# pcb.net
KiCad netlist of a schematic drawn in EAGLE
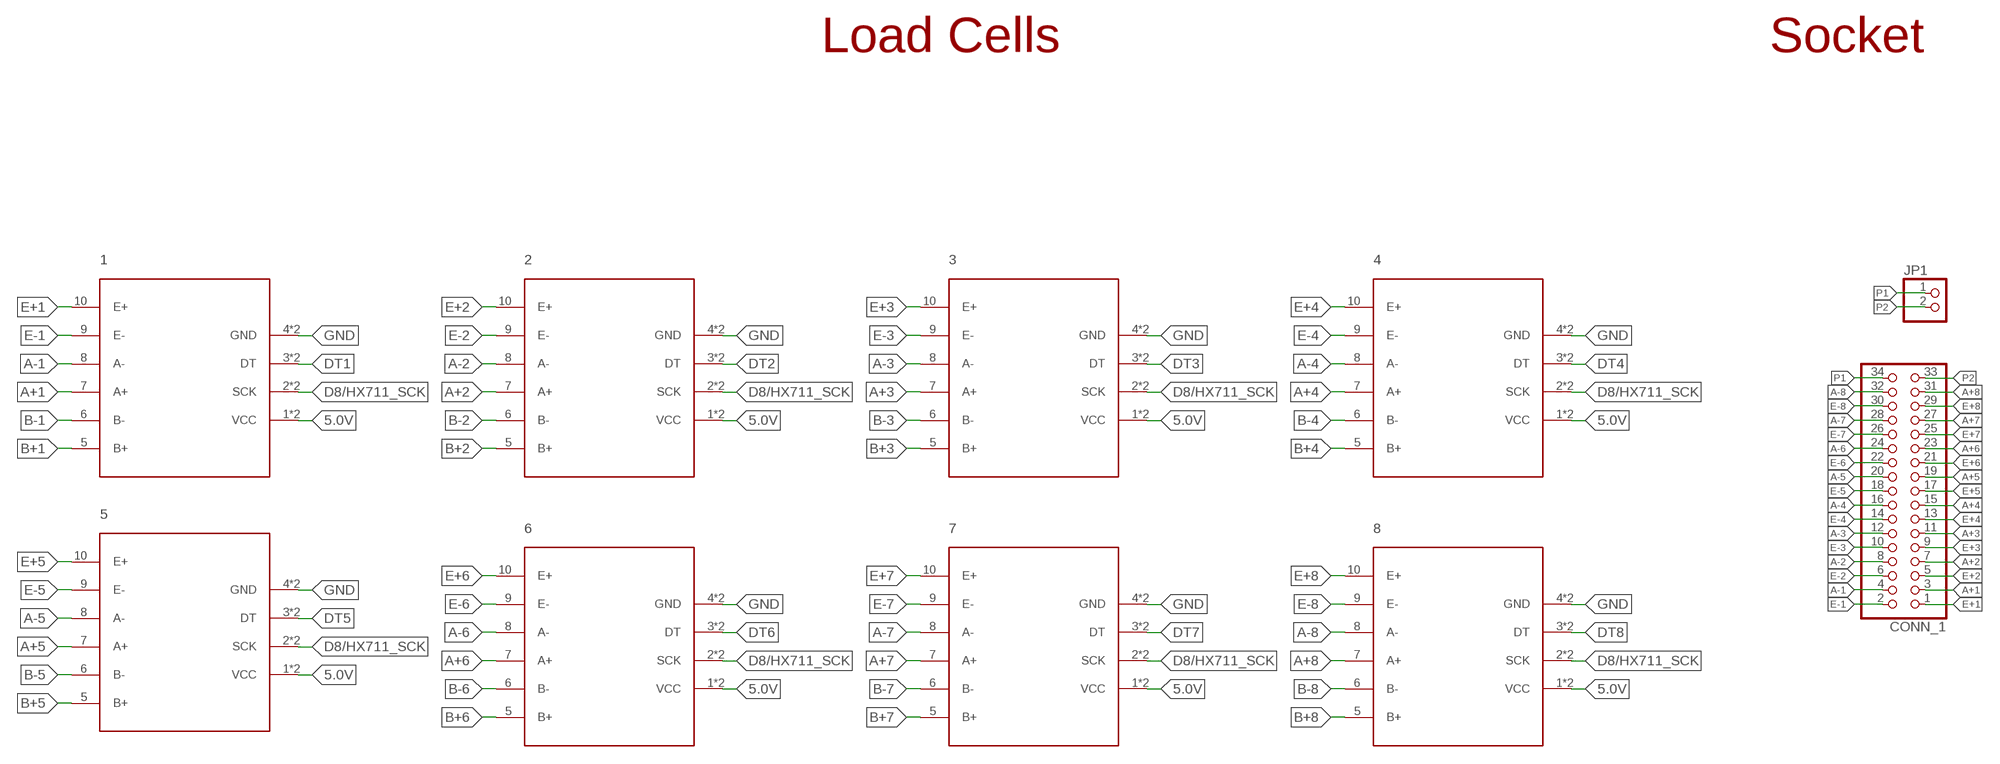
[diagram p0: schematic, sheet 1, part 1 of 2]
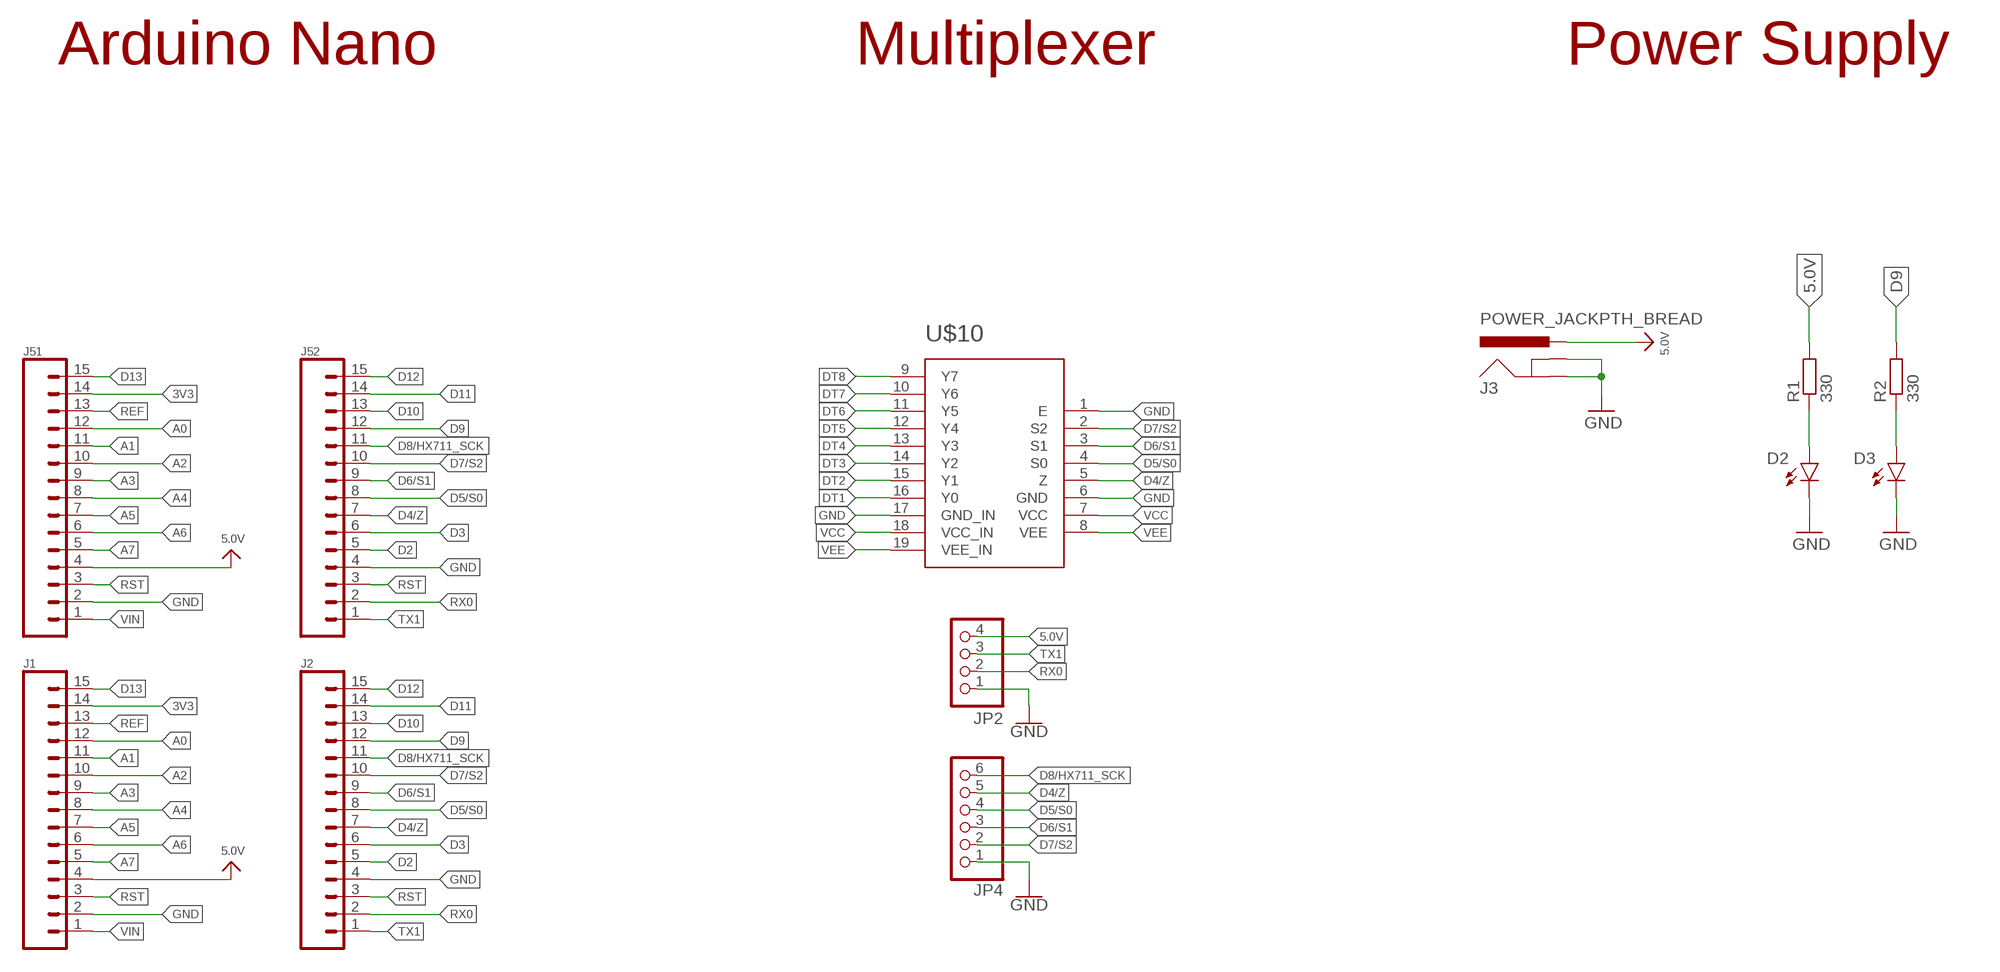
[diagram p1: schematic, sheet 1, part 2 of 2]

(export (version "E")
  (design (tool "Eeschema 10.0.6"))
  (components
    (comp (ref "1")
      (value "HX711")
      (footprint "eagle-import:HX711")
      (libsource (lib "eagle-import") (part "HX711"))
    )
    (comp (ref "2")
      (value "HX711")
      (footprint "eagle-import:HX711")
      (libsource (lib "eagle-import") (part "HX711"))
    )
    (comp (ref "3")
      (value "HX711")
      (footprint "eagle-import:HX711")
      (libsource (lib "eagle-import") (part "HX711"))
    )
    (comp (ref "4")
      (value "HX711")
      (footprint "eagle-import:HX711")
      (libsource (lib "eagle-import") (part "HX711"))
    )
    (comp (ref "5")
      (value "HX711")
      (footprint "eagle-import:HX711")
      (libsource (lib "eagle-import") (part "HX711"))
    )
    (comp (ref "6")
      (value "HX711")
      (footprint "eagle-import:HX711")
      (libsource (lib "eagle-import") (part "HX711"))
    )
    (comp (ref "7")
      (value "HX711")
      (footprint "eagle-import:HX711")
      (libsource (lib "eagle-import") (part "HX711"))
    )
    (comp (ref "8")
      (value "HX711")
      (footprint "eagle-import:HX711")
      (libsource (lib "eagle-import") (part "HX711"))
    )
    (comp (ref "CONN_1")
      (value "PINHD-2X17")
      (footprint "eagle-import:2X17")
      (libsource (lib "eagle-import") (part "PINHD-2X17"))
    )
    (comp (ref "D2")
      (value "LED5MM")
      (footprint "eagle-import:LED_5MM")
      (libsource (lib "eagle-import") (part "LED5MM"))
    )
    (comp (ref "D3")
      (value "LED5MM")
      (footprint "eagle-import:LED_5MM")
      (libsource (lib "eagle-import") (part "LED5MM"))
    )
    (comp (ref "J1")
      (value "CONN_15")
      (footprint "eagle-import:1X15")
      (fields (field (name "SPICEPREFIX") "X"))
      (libsource (lib "eagle-import") (part "CONN_15"))
    )
    (comp (ref "J2")
      (value "CONN_15")
      (footprint "eagle-import:1X15")
      (fields (field (name "SPICEPREFIX") "X"))
      (libsource (lib "eagle-import") (part "CONN_15"))
    )
    (comp (ref "J3")
      (value "POWER_JACKPTH_BREAD")
      (footprint "eagle-import:POWER_JACK_PTH_BREAD")
      (libsource (lib "eagle-import") (part "POWER_JACKPTH_BREAD"))
    )
    (comp (ref "J51")
      (value "CONN_15")
      (footprint "eagle-import:1X15")
      (fields (field (name "SPICEPREFIX") "X"))
      (libsource (lib "eagle-import") (part "CONN_15"))
    )
    (comp (ref "J52")
      (value "CONN_15")
      (footprint "eagle-import:1X15")
      (fields (field (name "SPICEPREFIX") "X"))
      (libsource (lib "eagle-import") (part "CONN_15"))
    )
    (comp (ref "JP1")
      (value "PINHD-1X2")
      (footprint "eagle-import:1X02")
      (libsource (lib "eagle-import") (part "PINHD-1X2"))
    )
    (comp (ref "JP2")
      (value "PINHD-1X4/90")
      (footprint "eagle-import:1X04_90")
      (libsource (lib "eagle-import") (part "PINHD-1X4/90"))
    )
    (comp (ref "JP4")
      (value "PINHD-1X6/90")
      (footprint "eagle-import:1X06_90")
      (libsource (lib "eagle-import") (part "PINHD-1X6/90"))
    )
    (comp (ref "R1")
      (value "330")
      (footprint "eagle-import:0204_7")
      (libsource (lib "eagle-import") (part "R-EU_0204/7"))
    )
    (comp (ref "R2")
      (value "330")
      (footprint "eagle-import:0204_7")
      (libsource (lib "eagle-import") (part "R-EU_0204/7"))
    )
    (comp (ref "U$10")
      (value "8CHMPLEX")
      (footprint "eagle-import:74HC4051")
      (libsource (lib "eagle-import") (part "8CHMPLEX"))
    )
  )
  (nets
    (net (code "1") (name "3V3") (class "Default")
      (node (ref "J1") (pin "14") (pinfunction "14_14") (pintype "passive"))
      (node (ref "J51") (pin "14") (pinfunction "14_14") (pintype "passive"))
    )
    (net (code "2") (name "5.0V") (class "Default")
      (node (ref "1") (pin "1") (pinfunction "VCC_1") (pintype "power_in"))
      (node (ref "1") (pin "1.2") (pinfunction "VCC_1.2") (pintype "power_in"))
      (node (ref "2") (pin "1") (pinfunction "VCC_1") (pintype "power_in"))
      (node (ref "2") (pin "1.2") (pinfunction "VCC_1.2") (pintype "power_in"))
      (node (ref "3") (pin "1") (pinfunction "VCC_1") (pintype "power_in"))
      (node (ref "3") (pin "1.2") (pinfunction "VCC_1.2") (pintype "power_in"))
      (node (ref "4") (pin "1") (pinfunction "VCC_1") (pintype "power_in"))
      (node (ref "4") (pin "1.2") (pinfunction "VCC_1.2") (pintype "power_in"))
      (node (ref "5") (pin "1") (pinfunction "VCC_1") (pintype "power_in"))
      (node (ref "5") (pin "1.2") (pinfunction "VCC_1.2") (pintype "power_in"))
      (node (ref "6") (pin "1") (pinfunction "VCC_1") (pintype "power_in"))
      (node (ref "6") (pin "1.2") (pinfunction "VCC_1.2") (pintype "power_in"))
      (node (ref "7") (pin "1") (pinfunction "VCC_1") (pintype "power_in"))
      (node (ref "7") (pin "1.2") (pinfunction "VCC_1.2") (pintype "power_in"))
      (node (ref "8") (pin "1") (pinfunction "VCC_1") (pintype "power_in"))
      (node (ref "8") (pin "1.2") (pinfunction "VCC_1.2") (pintype "power_in"))
      (node (ref "J1") (pin "4") (pinfunction "4_4") (pintype "passive"))
      (node (ref "J3") (pin "PWR") (pinfunction "PWR_PWR") (pintype "bidirectional"))
      (node (ref "J51") (pin "4") (pinfunction "4_4") (pintype "passive"))
      (node (ref "JP2") (pin "4") (pinfunction "4_4") (pintype "passive"))
      (node (ref "R1") (pin "2") (pinfunction "2_2") (pintype "passive"))
    )
    (net (code "3") (name "A+1") (class "Default")
      (node (ref "1") (pin "7") (pinfunction "A+_7") (pintype "input"))
      (node (ref "CONN_1") (pin "3") (pinfunction "3_3") (pintype "passive"))
    )
    (net (code "4") (name "A+2") (class "Default")
      (node (ref "2") (pin "7") (pinfunction "A+_7") (pintype "input"))
      (node (ref "CONN_1") (pin "7") (pinfunction "7_7") (pintype "passive"))
    )
    (net (code "5") (name "A+3") (class "Default")
      (node (ref "3") (pin "7") (pinfunction "A+_7") (pintype "input"))
      (node (ref "CONN_1") (pin "11") (pinfunction "11_11") (pintype "passive"))
    )
    (net (code "6") (name "A+4") (class "Default")
      (node (ref "4") (pin "7") (pinfunction "A+_7") (pintype "input"))
      (node (ref "CONN_1") (pin "15") (pinfunction "15_15") (pintype "passive"))
    )
    (net (code "7") (name "A+5") (class "Default")
      (node (ref "5") (pin "7") (pinfunction "A+_7") (pintype "input"))
      (node (ref "CONN_1") (pin "19") (pinfunction "19_19") (pintype "passive"))
    )
    (net (code "8") (name "A+6") (class "Default")
      (node (ref "6") (pin "7") (pinfunction "A+_7") (pintype "input"))
      (node (ref "CONN_1") (pin "23") (pinfunction "23_23") (pintype "passive"))
    )
    (net (code "9") (name "A+7") (class "Default")
      (node (ref "7") (pin "7") (pinfunction "A+_7") (pintype "input"))
      (node (ref "CONN_1") (pin "27") (pinfunction "27_27") (pintype "passive"))
    )
    (net (code "10") (name "A+8") (class "Default")
      (node (ref "8") (pin "7") (pinfunction "A+_7") (pintype "input"))
      (node (ref "CONN_1") (pin "31") (pinfunction "31_31") (pintype "passive"))
    )
    (net (code "11") (name "A-1") (class "Default")
      (node (ref "1") (pin "8") (pinfunction "A-_8") (pintype "input"))
      (node (ref "CONN_1") (pin "4") (pinfunction "4_4") (pintype "passive"))
    )
    (net (code "12") (name "A-2") (class "Default")
      (node (ref "2") (pin "8") (pinfunction "A-_8") (pintype "input"))
      (node (ref "CONN_1") (pin "8") (pinfunction "8_8") (pintype "passive"))
    )
    (net (code "13") (name "A-3") (class "Default")
      (node (ref "3") (pin "8") (pinfunction "A-_8") (pintype "input"))
      (node (ref "CONN_1") (pin "12") (pinfunction "12_12") (pintype "passive"))
    )
    (net (code "14") (name "A-4") (class "Default")
      (node (ref "4") (pin "8") (pinfunction "A-_8") (pintype "input"))
      (node (ref "CONN_1") (pin "16") (pinfunction "16_16") (pintype "passive"))
    )
    (net (code "15") (name "A-5") (class "Default")
      (node (ref "5") (pin "8") (pinfunction "A-_8") (pintype "input"))
      (node (ref "CONN_1") (pin "20") (pinfunction "20_20") (pintype "passive"))
    )
    (net (code "16") (name "A-6") (class "Default")
      (node (ref "6") (pin "8") (pinfunction "A-_8") (pintype "input"))
      (node (ref "CONN_1") (pin "24") (pinfunction "24_24") (pintype "passive"))
    )
    (net (code "17") (name "A-7") (class "Default")
      (node (ref "7") (pin "8") (pinfunction "A-_8") (pintype "input"))
      (node (ref "CONN_1") (pin "28") (pinfunction "28_28") (pintype "passive"))
    )
    (net (code "18") (name "A-8") (class "Default")
      (node (ref "8") (pin "8") (pinfunction "A-_8") (pintype "input"))
      (node (ref "CONN_1") (pin "32") (pinfunction "32_32") (pintype "passive"))
    )
    (net (code "19") (name "A0") (class "Default")
      (node (ref "J1") (pin "12") (pinfunction "12_12") (pintype "passive"))
      (node (ref "J51") (pin "12") (pinfunction "12_12") (pintype "passive"))
    )
    (net (code "20") (name "A1") (class "Default")
      (node (ref "J1") (pin "11") (pinfunction "11_11") (pintype "passive"))
      (node (ref "J51") (pin "11") (pinfunction "11_11") (pintype "passive"))
    )
    (net (code "21") (name "A2") (class "Default")
      (node (ref "J1") (pin "10") (pinfunction "10_10") (pintype "passive"))
      (node (ref "J51") (pin "10") (pinfunction "10_10") (pintype "passive"))
    )
    (net (code "22") (name "A3") (class "Default")
      (node (ref "J1") (pin "9") (pinfunction "9_9") (pintype "passive"))
      (node (ref "J51") (pin "9") (pinfunction "9_9") (pintype "passive"))
    )
    (net (code "23") (name "A4") (class "Default")
      (node (ref "J1") (pin "8") (pinfunction "8_8") (pintype "passive"))
      (node (ref "J51") (pin "8") (pinfunction "8_8") (pintype "passive"))
    )
    (net (code "24") (name "A5") (class "Default")
      (node (ref "J1") (pin "7") (pinfunction "7_7") (pintype "passive"))
      (node (ref "J51") (pin "7") (pinfunction "7_7") (pintype "passive"))
    )
    (net (code "25") (name "A6") (class "Default")
      (node (ref "J1") (pin "6") (pinfunction "6_6") (pintype "passive"))
      (node (ref "J51") (pin "6") (pinfunction "6_6") (pintype "passive"))
    )
    (net (code "26") (name "A7") (class "Default")
      (node (ref "J1") (pin "5") (pinfunction "5_5") (pintype "passive"))
      (node (ref "J51") (pin "5") (pinfunction "5_5") (pintype "passive"))
    )
    (net (code "27") (name "B+1") (class "Default")
      (node (ref "1") (pin "5") (pinfunction "B+_5") (pintype "input"))
    )
    (net (code "28") (name "B+2") (class "Default")
      (node (ref "2") (pin "5") (pinfunction "B+_5") (pintype "input"))
    )
    (net (code "29") (name "B+3") (class "Default")
      (node (ref "3") (pin "5") (pinfunction "B+_5") (pintype "input"))
    )
    (net (code "30") (name "B+4") (class "Default")
      (node (ref "4") (pin "5") (pinfunction "B+_5") (pintype "input"))
    )
    (net (code "31") (name "B+5") (class "Default")
      (node (ref "5") (pin "5") (pinfunction "B+_5") (pintype "input"))
    )
    (net (code "32") (name "B+6") (class "Default")
      (node (ref "6") (pin "5") (pinfunction "B+_5") (pintype "input"))
    )
    (net (code "33") (name "B+7") (class "Default")
      (node (ref "7") (pin "5") (pinfunction "B+_5") (pintype "input"))
    )
    (net (code "34") (name "B+8") (class "Default")
      (node (ref "8") (pin "5") (pinfunction "B+_5") (pintype "input"))
    )
    (net (code "35") (name "B-1") (class "Default")
      (node (ref "1") (pin "6") (pinfunction "B-_6") (pintype "input"))
    )
    (net (code "36") (name "B-2") (class "Default")
      (node (ref "2") (pin "6") (pinfunction "B-_6") (pintype "input"))
    )
    (net (code "37") (name "B-3") (class "Default")
      (node (ref "3") (pin "6") (pinfunction "B-_6") (pintype "input"))
    )
    (net (code "38") (name "B-4") (class "Default")
      (node (ref "4") (pin "6") (pinfunction "B-_6") (pintype "input"))
    )
    (net (code "39") (name "B-5") (class "Default")
      (node (ref "5") (pin "6") (pinfunction "B-_6") (pintype "input"))
    )
    (net (code "40") (name "B-6") (class "Default")
      (node (ref "6") (pin "6") (pinfunction "B-_6") (pintype "input"))
    )
    (net (code "41") (name "B-7") (class "Default")
      (node (ref "7") (pin "6") (pinfunction "B-_6") (pintype "input"))
    )
    (net (code "42") (name "B-8") (class "Default")
      (node (ref "8") (pin "6") (pinfunction "B-_6") (pintype "input"))
    )
    (net (code "43") (name "D2") (class "Default")
      (node (ref "J2") (pin "5") (pinfunction "5_5") (pintype "passive"))
      (node (ref "J52") (pin "5") (pinfunction "5_5") (pintype "passive"))
    )
    (net (code "44") (name "D3") (class "Default")
      (node (ref "J2") (pin "6") (pinfunction "6_6") (pintype "passive"))
      (node (ref "J52") (pin "6") (pinfunction "6_6") (pintype "passive"))
    )
    (net (code "45") (name "D4{slash}Z") (class "Default")
      (node (ref "J2") (pin "7") (pinfunction "7_7") (pintype "passive"))
      (node (ref "J52") (pin "7") (pinfunction "7_7") (pintype "passive"))
      (node (ref "JP4") (pin "5") (pinfunction "5_5") (pintype "passive"))
      (node (ref "U$10") (pin "5") (pinfunction "Z_5") (pintype "output"))
    )
    (net (code "46") (name "D5{slash}S0") (class "Default")
      (node (ref "J2") (pin "8") (pinfunction "8_8") (pintype "passive"))
      (node (ref "J52") (pin "8") (pinfunction "8_8") (pintype "passive"))
      (node (ref "JP4") (pin "4") (pinfunction "4_4") (pintype "passive"))
      (node (ref "U$10") (pin "4") (pinfunction "S0_4") (pintype "output"))
    )
    (net (code "47") (name "D6{slash}S1") (class "Default")
      (node (ref "J2") (pin "9") (pinfunction "9_9") (pintype "passive"))
      (node (ref "J52") (pin "9") (pinfunction "9_9") (pintype "passive"))
      (node (ref "JP4") (pin "3") (pinfunction "3_3") (pintype "passive"))
      (node (ref "U$10") (pin "3") (pinfunction "S1_3") (pintype "output"))
    )
    (net (code "48") (name "D7{slash}S2") (class "Default")
      (node (ref "J2") (pin "10") (pinfunction "10_10") (pintype "passive"))
      (node (ref "J52") (pin "10") (pinfunction "10_10") (pintype "passive"))
      (node (ref "JP4") (pin "2") (pinfunction "2_2") (pintype "passive"))
      (node (ref "U$10") (pin "2") (pinfunction "S2_2") (pintype "output"))
    )
    (net (code "49") (name "D8{slash}HX711_SCK") (class "Default")
      (node (ref "1") (pin "2") (pinfunction "SCK_2") (pintype "output"))
      (node (ref "1") (pin "2.2") (pinfunction "SCK_2.2") (pintype "output"))
      (node (ref "2") (pin "2") (pinfunction "SCK_2") (pintype "output"))
      (node (ref "2") (pin "2.2") (pinfunction "SCK_2.2") (pintype "output"))
      (node (ref "3") (pin "2") (pinfunction "SCK_2") (pintype "output"))
      (node (ref "3") (pin "2.2") (pinfunction "SCK_2.2") (pintype "output"))
      (node (ref "4") (pin "2") (pinfunction "SCK_2") (pintype "output"))
      (node (ref "4") (pin "2.2") (pinfunction "SCK_2.2") (pintype "output"))
      (node (ref "5") (pin "2") (pinfunction "SCK_2") (pintype "output"))
      (node (ref "5") (pin "2.2") (pinfunction "SCK_2.2") (pintype "output"))
      (node (ref "6") (pin "2") (pinfunction "SCK_2") (pintype "output"))
      (node (ref "6") (pin "2.2") (pinfunction "SCK_2.2") (pintype "output"))
      (node (ref "7") (pin "2") (pinfunction "SCK_2") (pintype "output"))
      (node (ref "7") (pin "2.2") (pinfunction "SCK_2.2") (pintype "output"))
      (node (ref "8") (pin "2") (pinfunction "SCK_2") (pintype "output"))
      (node (ref "8") (pin "2.2") (pinfunction "SCK_2.2") (pintype "output"))
      (node (ref "J2") (pin "11") (pinfunction "11_11") (pintype "passive"))
      (node (ref "J52") (pin "11") (pinfunction "11_11") (pintype "passive"))
      (node (ref "JP4") (pin "6") (pinfunction "6_6") (pintype "passive"))
    )
    (net (code "50") (name "D9") (class "Default")
      (node (ref "J2") (pin "12") (pinfunction "12_12") (pintype "passive"))
      (node (ref "J52") (pin "12") (pinfunction "12_12") (pintype "passive"))
      (node (ref "R2") (pin "2") (pinfunction "2_2") (pintype "passive"))
    )
    (net (code "51") (name "D10") (class "Default")
      (node (ref "J2") (pin "13") (pinfunction "13_13") (pintype "passive"))
      (node (ref "J52") (pin "13") (pinfunction "13_13") (pintype "passive"))
    )
    (net (code "52") (name "D11") (class "Default")
      (node (ref "J2") (pin "14") (pinfunction "14_14") (pintype "passive"))
      (node (ref "J52") (pin "14") (pinfunction "14_14") (pintype "passive"))
    )
    (net (code "53") (name "D12") (class "Default")
      (node (ref "J2") (pin "15") (pinfunction "15_15") (pintype "passive"))
      (node (ref "J52") (pin "15") (pinfunction "15_15") (pintype "passive"))
    )
    (net (code "54") (name "D13") (class "Default")
      (node (ref "J1") (pin "15") (pinfunction "15_15") (pintype "passive"))
      (node (ref "J51") (pin "15") (pinfunction "15_15") (pintype "passive"))
    )
    (net (code "55") (name "DT1") (class "Default")
      (node (ref "1") (pin "3") (pinfunction "DT_3") (pintype "output"))
      (node (ref "1") (pin "3.2") (pinfunction "DT_3.2") (pintype "output"))
      (node (ref "U$10") (pin "16") (pinfunction "Y0_16") (pintype "input"))
    )
    (net (code "56") (name "DT2") (class "Default")
      (node (ref "2") (pin "3") (pinfunction "DT_3") (pintype "output"))
      (node (ref "2") (pin "3.2") (pinfunction "DT_3.2") (pintype "output"))
      (node (ref "U$10") (pin "15") (pinfunction "Y1_15") (pintype "input"))
    )
    (net (code "57") (name "DT3") (class "Default")
      (node (ref "3") (pin "3") (pinfunction "DT_3") (pintype "output"))
      (node (ref "3") (pin "3.2") (pinfunction "DT_3.2") (pintype "output"))
      (node (ref "U$10") (pin "14") (pinfunction "Y2_14") (pintype "input"))
    )
    (net (code "58") (name "DT4") (class "Default")
      (node (ref "4") (pin "3") (pinfunction "DT_3") (pintype "output"))
      (node (ref "4") (pin "3.2") (pinfunction "DT_3.2") (pintype "output"))
      (node (ref "U$10") (pin "13") (pinfunction "Y3_13") (pintype "input"))
    )
    (net (code "59") (name "DT5") (class "Default")
      (node (ref "5") (pin "3") (pinfunction "DT_3") (pintype "output"))
      (node (ref "5") (pin "3.2") (pinfunction "DT_3.2") (pintype "output"))
      (node (ref "U$10") (pin "12") (pinfunction "Y4_12") (pintype "input"))
    )
    (net (code "60") (name "DT6") (class "Default")
      (node (ref "6") (pin "3") (pinfunction "DT_3") (pintype "output"))
      (node (ref "6") (pin "3.2") (pinfunction "DT_3.2") (pintype "output"))
      (node (ref "U$10") (pin "11") (pinfunction "Y5_11") (pintype "input"))
    )
    (net (code "61") (name "DT7") (class "Default")
      (node (ref "7") (pin "3") (pinfunction "DT_3") (pintype "output"))
      (node (ref "7") (pin "3.2") (pinfunction "DT_3.2") (pintype "output"))
      (node (ref "U$10") (pin "10") (pinfunction "Y6_10") (pintype "input"))
    )
    (net (code "62") (name "DT8") (class "Default")
      (node (ref "8") (pin "3") (pinfunction "DT_3") (pintype "output"))
      (node (ref "8") (pin "3.2") (pinfunction "DT_3.2") (pintype "output"))
      (node (ref "U$10") (pin "9") (pinfunction "Y7_9") (pintype "input"))
    )
    (net (code "63") (name "E+1") (class "Default")
      (node (ref "1") (pin "10") (pinfunction "E+_10") (pintype "input"))
      (node (ref "CONN_1") (pin "1") (pinfunction "1_1") (pintype "passive"))
    )
    (net (code "64") (name "E+2") (class "Default")
      (node (ref "2") (pin "10") (pinfunction "E+_10") (pintype "input"))
      (node (ref "CONN_1") (pin "5") (pinfunction "5_5") (pintype "passive"))
    )
    (net (code "65") (name "E+3") (class "Default")
      (node (ref "3") (pin "10") (pinfunction "E+_10") (pintype "input"))
      (node (ref "CONN_1") (pin "9") (pinfunction "9_9") (pintype "passive"))
    )
    (net (code "66") (name "E+4") (class "Default")
      (node (ref "4") (pin "10") (pinfunction "E+_10") (pintype "input"))
      (node (ref "CONN_1") (pin "13") (pinfunction "13_13") (pintype "passive"))
    )
    (net (code "67") (name "E+5") (class "Default")
      (node (ref "5") (pin "10") (pinfunction "E+_10") (pintype "input"))
      (node (ref "CONN_1") (pin "17") (pinfunction "17_17") (pintype "passive"))
    )
    (net (code "68") (name "E+6") (class "Default")
      (node (ref "6") (pin "10") (pinfunction "E+_10") (pintype "input"))
      (node (ref "CONN_1") (pin "21") (pinfunction "21_21") (pintype "passive"))
    )
    (net (code "69") (name "E+7") (class "Default")
      (node (ref "7") (pin "10") (pinfunction "E+_10") (pintype "input"))
      (node (ref "CONN_1") (pin "25") (pinfunction "25_25") (pintype "passive"))
    )
    (net (code "70") (name "E+8") (class "Default")
      (node (ref "8") (pin "10") (pinfunction "E+_10") (pintype "input"))
      (node (ref "CONN_1") (pin "29") (pinfunction "29_29") (pintype "passive"))
    )
    (net (code "71") (name "E-1") (class "Default")
      (node (ref "1") (pin "9") (pinfunction "E-_9") (pintype "input"))
      (node (ref "CONN_1") (pin "2") (pinfunction "2_2") (pintype "passive"))
    )
    (net (code "72") (name "E-2") (class "Default")
      (node (ref "2") (pin "9") (pinfunction "E-_9") (pintype "input"))
      (node (ref "CONN_1") (pin "6") (pinfunction "6_6") (pintype "passive"))
    )
    (net (code "73") (name "E-3") (class "Default")
      (node (ref "3") (pin "9") (pinfunction "E-_9") (pintype "input"))
      (node (ref "CONN_1") (pin "10") (pinfunction "10_10") (pintype "passive"))
    )
    (net (code "74") (name "E-4") (class "Default")
      (node (ref "4") (pin "9") (pinfunction "E-_9") (pintype "input"))
      (node (ref "CONN_1") (pin "14") (pinfunction "14_14") (pintype "passive"))
    )
    (net (code "75") (name "E-5") (class "Default")
      (node (ref "5") (pin "9") (pinfunction "E-_9") (pintype "input"))
      (node (ref "CONN_1") (pin "18") (pinfunction "18_18") (pintype "passive"))
    )
    (net (code "76") (name "E-6") (class "Default")
      (node (ref "6") (pin "9") (pinfunction "E-_9") (pintype "input"))
      (node (ref "CONN_1") (pin "22") (pinfunction "22_22") (pintype "passive"))
    )
    (net (code "77") (name "E-7") (class "Default")
      (node (ref "7") (pin "9") (pinfunction "E-_9") (pintype "input"))
      (node (ref "CONN_1") (pin "26") (pinfunction "26_26") (pintype "passive"))
    )
    (net (code "78") (name "E-8") (class "Default")
      (node (ref "8") (pin "9") (pinfunction "E-_9") (pintype "input"))
      (node (ref "CONN_1") (pin "30") (pinfunction "30_30") (pintype "passive"))
    )
    (net (code "79") (name "GND") (class "Default")
      (node (ref "1") (pin "4") (pinfunction "GND_4") (pintype "power_in"))
      (node (ref "1") (pin "4.2") (pinfunction "GND_4.2") (pintype "power_in"))
      (node (ref "2") (pin "4") (pinfunction "GND_4") (pintype "power_in"))
      (node (ref "2") (pin "4.2") (pinfunction "GND_4.2") (pintype "power_in"))
      (node (ref "3") (pin "4") (pinfunction "GND_4") (pintype "power_in"))
      (node (ref "3") (pin "4.2") (pinfunction "GND_4.2") (pintype "power_in"))
      (node (ref "4") (pin "4") (pinfunction "GND_4") (pintype "power_in"))
      (node (ref "4") (pin "4.2") (pinfunction "GND_4.2") (pintype "power_in"))
      (node (ref "5") (pin "4") (pinfunction "GND_4") (pintype "power_in"))
      (node (ref "5") (pin "4.2") (pinfunction "GND_4.2") (pintype "power_in"))
      (node (ref "6") (pin "4") (pinfunction "GND_4") (pintype "power_in"))
      (node (ref "6") (pin "4.2") (pinfunction "GND_4.2") (pintype "power_in"))
      (node (ref "7") (pin "4") (pinfunction "GND_4") (pintype "power_in"))
      (node (ref "7") (pin "4.2") (pinfunction "GND_4.2") (pintype "power_in"))
      (node (ref "8") (pin "4") (pinfunction "GND_4") (pintype "power_in"))
      (node (ref "8") (pin "4.2") (pinfunction "GND_4.2") (pintype "power_in"))
      (node (ref "D2") (pin "K") (pinfunction "C_K") (pintype "passive"))
      (node (ref "D3") (pin "K") (pinfunction "C_K") (pintype "passive"))
      (node (ref "J1") (pin "2") (pinfunction "2_2") (pintype "passive"))
      (node (ref "J2") (pin "4") (pinfunction "4_4") (pintype "passive"))
      (node (ref "J3") (pin "GND") (pinfunction "GND_GND") (pintype "bidirectional"))
      (node (ref "J3") (pin "GNDBREAK") (pinfunction "GNDBREAK_GNDBREAK") (pintype "bidirectional"))
      (node (ref "J51") (pin "2") (pinfunction "2_2") (pintype "passive"))
      (node (ref "J52") (pin "4") (pinfunction "4_4") (pintype "passive"))
      (node (ref "JP2") (pin "1") (pinfunction "1_1") (pintype "passive"))
      (node (ref "JP4") (pin "1") (pinfunction "1_1") (pintype "passive"))
      (node (ref "U$10") (pin "1") (pinfunction "E_1") (pintype "output"))
      (node (ref "U$10") (pin "17") (pinfunction "GND_IN_17") (pintype "power_in"))
      (node (ref "U$10") (pin "6") (pinfunction "GND_6") (pintype "power_in"))
    )
    (net (code "80") (name "Net-(D2-PadA)") (class "Default")
      (node (ref "D2") (pin "A") (pinfunction "A_A") (pintype "passive"))
      (node (ref "R1") (pin "1") (pinfunction "1_1") (pintype "passive"))
    )
    (net (code "81") (name "Net-(D3-PadA)") (class "Default")
      (node (ref "D3") (pin "A") (pinfunction "A_A") (pintype "passive"))
      (node (ref "R2") (pin "1") (pinfunction "1_1") (pintype "passive"))
    )
    (net (code "82") (name "P1") (class "Default")
      (node (ref "CONN_1") (pin "34") (pinfunction "34_34") (pintype "passive"))
      (node (ref "JP1") (pin "1") (pinfunction "1_1") (pintype "passive"))
    )
    (net (code "83") (name "P2") (class "Default")
      (node (ref "CONN_1") (pin "33") (pinfunction "33_33") (pintype "passive"))
      (node (ref "JP1") (pin "2") (pinfunction "2_2") (pintype "passive"))
    )
    (net (code "84") (name "REF") (class "Default")
      (node (ref "J1") (pin "13") (pinfunction "13_13") (pintype "passive"))
      (node (ref "J51") (pin "13") (pinfunction "13_13") (pintype "passive"))
    )
    (net (code "85") (name "RST") (class "Default")
      (node (ref "J1") (pin "3") (pinfunction "3_3") (pintype "passive"))
      (node (ref "J2") (pin "3") (pinfunction "3_3") (pintype "passive"))
      (node (ref "J51") (pin "3") (pinfunction "3_3") (pintype "passive"))
      (node (ref "J52") (pin "3") (pinfunction "3_3") (pintype "passive"))
    )
    (net (code "86") (name "RX0") (class "Default")
      (node (ref "J2") (pin "2") (pinfunction "2_2") (pintype "passive"))
      (node (ref "J52") (pin "2") (pinfunction "2_2") (pintype "passive"))
      (node (ref "JP2") (pin "2") (pinfunction "2_2") (pintype "passive"))
    )
    (net (code "87") (name "TX1") (class "Default")
      (node (ref "J2") (pin "1") (pinfunction "1_1") (pintype "passive"))
      (node (ref "J52") (pin "1") (pinfunction "1_1") (pintype "passive"))
      (node (ref "JP2") (pin "3") (pinfunction "3_3") (pintype "passive"))
    )
    (net (code "88") (name "VCC") (class "Default")
      (node (ref "U$10") (pin "18") (pinfunction "VCC_IN_18") (pintype "power_in"))
      (node (ref "U$10") (pin "7") (pinfunction "VCC_7") (pintype "power_in"))
    )
    (net (code "89") (name "VEE") (class "Default")
      (node (ref "U$10") (pin "19") (pinfunction "VEE_IN_19") (pintype "power_in"))
      (node (ref "U$10") (pin "8") (pinfunction "VEE_8") (pintype "power_in"))
    )
    (net (code "90") (name "VIN") (class "Default")
      (node (ref "J1") (pin "1") (pinfunction "1_1") (pintype "passive"))
      (node (ref "J51") (pin "1") (pinfunction "1_1") (pintype "passive"))
    )
  )
)
